# IO.net
KiCad netlist of a schematic drawn in EAGLE
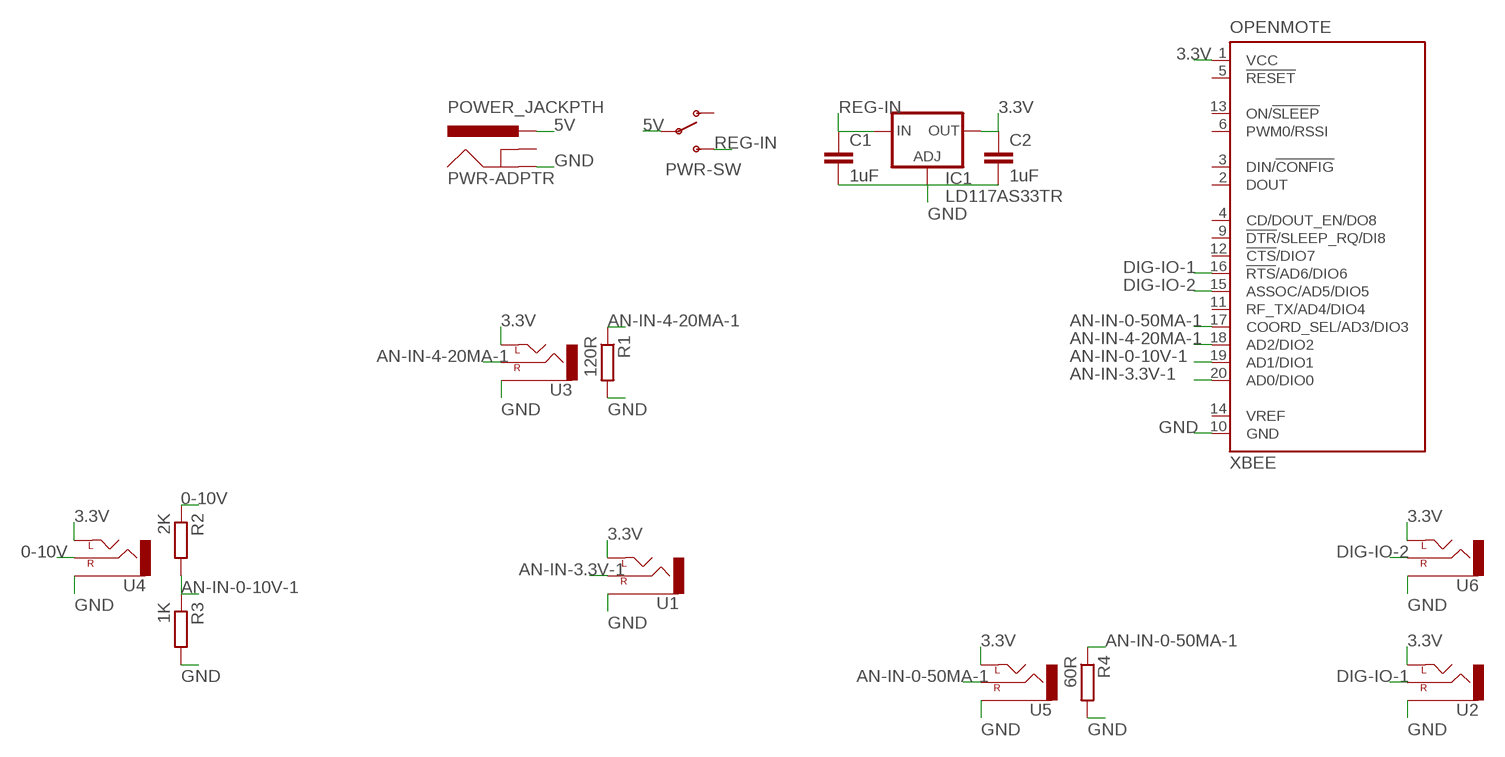
[diagram p0: schematic, sheet 1]

(export (version "E")
  (design (tool "Eeschema 10.0.6"))
  (components
    (comp (ref "C1")
      (value "1uF")
      (footprint "eagle-import:C0805")
      (libsource (lib "eagle-import") (part "C-EUC0805"))
    )
    (comp (ref "C2")
      (value "1uF")
      (footprint "eagle-import:C0805")
      (libsource (lib "eagle-import") (part "C-EUC0805"))
    )
    (comp (ref "IC1")
      (value "LD117AS33TR")
      (footprint "eagle-import:SOT223")
      (libsource (lib "eagle-import") (part "LD117A?S33TR"))
    )
    (comp (ref "OPENMOTE")
      (value "XBEE")
      (footprint "eagle-import:XBEE")
      (fields (field (name "MPN") "XBP24-Z7UIT-004"))
      (libsource (lib "eagle-import") (part "XBEE"))
    )
    (comp (ref "PWR-ADPTR")
      (value "POWER_JACKPTH")
      (footprint "eagle-import:POWER_JACK_PTH")
      (libsource (lib "eagle-import") (part "POWER_JACKPTH"))
    )
    (comp (ref "PWR-SW")
      (value "SWITCH-SPDTSMD2")
      (footprint "eagle-import:SWITCH-SPDT-SMD")
      (libsource (lib "eagle-import") (part "SWITCH-SPDTSMD2"))
    )
    (comp (ref "R1")
      (value "120R")
      (footprint "eagle-import:M0805")
      (libsource (lib "eagle-import") (part "R-EU_M0805"))
    )
    (comp (ref "R2")
      (value "2K")
      (footprint "eagle-import:M0805")
      (libsource (lib "eagle-import") (part "R-EU_M0805"))
    )
    (comp (ref "R3")
      (value "1K")
      (footprint "eagle-import:M0805")
      (libsource (lib "eagle-import") (part "R-EU_M0805"))
    )
    (comp (ref "R4")
      (value "60R")
      (footprint "eagle-import:M0805")
      (libsource (lib "eagle-import") (part "R-EU_M0805"))
    )
    (comp (ref "U1")
      (value "AUDIO-JACKSMD2")
      (footprint "eagle-import:AUDIO-JACK-3.5MM-SMD")
      (libsource (lib "eagle-import") (part "AUDIO-JACKSMD2"))
    )
    (comp (ref "U2")
      (value "AUDIO-JACKSMD2")
      (footprint "eagle-import:AUDIO-JACK-3.5MM-SMD")
      (libsource (lib "eagle-import") (part "AUDIO-JACKSMD2"))
    )
    (comp (ref "U3")
      (value "AUDIO-JACKSMD2")
      (footprint "eagle-import:AUDIO-JACK-3.5MM-SMD")
      (libsource (lib "eagle-import") (part "AUDIO-JACKSMD2"))
    )
    (comp (ref "U4")
      (value "AUDIO-JACKSMD2")
      (footprint "eagle-import:AUDIO-JACK-3.5MM-SMD")
      (libsource (lib "eagle-import") (part "AUDIO-JACKSMD2"))
    )
    (comp (ref "U5")
      (value "AUDIO-JACKSMD2")
      (footprint "eagle-import:AUDIO-JACK-3.5MM-SMD")
      (libsource (lib "eagle-import") (part "AUDIO-JACKSMD2"))
    )
    (comp (ref "U6")
      (value "AUDIO-JACKSMD2")
      (footprint "eagle-import:AUDIO-JACK-3.5MM-SMD")
      (libsource (lib "eagle-import") (part "AUDIO-JACKSMD2"))
    )
  )
  (nets
    (net (code "1") (name "/0-10V") (class "Default")
      (node (ref "R2") (pin "1") (pinfunction "1_1") (pintype "passive"))
      (node (ref "U4") (pin "RING") (pinfunction "RIGHT_RING") (pintype "bidirectional"))
    )
    (net (code "2") (name "/3.3V") (class "Default")
      (node (ref "C2") (pin "1") (pinfunction "1_1") (pintype "passive"))
      (node (ref "IC1") (pin "4") (pinfunction "OUT_4") (pintype "passive"))
      (node (ref "OPENMOTE") (pin "1") (pinfunction "VCC_1") (pintype "power_in"))
      (node (ref "U1") (pin "TIP") (pinfunction "LEFT_TIP") (pintype "bidirectional"))
      (node (ref "U2") (pin "TIP") (pinfunction "LEFT_TIP") (pintype "bidirectional"))
      (node (ref "U3") (pin "TIP") (pinfunction "LEFT_TIP") (pintype "bidirectional"))
      (node (ref "U4") (pin "TIP") (pinfunction "LEFT_TIP") (pintype "bidirectional"))
      (node (ref "U5") (pin "TIP") (pinfunction "LEFT_TIP") (pintype "bidirectional"))
      (node (ref "U6") (pin "TIP") (pinfunction "LEFT_TIP") (pintype "bidirectional"))
    )
    (net (code "3") (name "/5V") (class "Default")
      (node (ref "PWR-ADPTR") (pin "PWR") (pinfunction "PWR_PWR") (pintype "bidirectional"))
      (node (ref "PWR-SW") (pin "2") (pinfunction "P_2") (pintype "passive"))
    )
    (net (code "4") (name "/AN-IN-0-10V-1") (class "Default")
      (node (ref "OPENMOTE") (pin "19") (pinfunction "AD1/DIO1_19") (pintype "bidirectional"))
      (node (ref "R2") (pin "2") (pinfunction "2_2") (pintype "passive"))
      (node (ref "R3") (pin "1") (pinfunction "1_1") (pintype "passive"))
    )
    (net (code "5") (name "/AN-IN-0-50MA-1") (class "Default")
      (node (ref "OPENMOTE") (pin "17") (pinfunction "COORD_SEL/AD3/DIO3_17") (pintype "bidirectional"))
      (node (ref "R4") (pin "1") (pinfunction "1_1") (pintype "passive"))
      (node (ref "U5") (pin "RING") (pinfunction "RIGHT_RING") (pintype "bidirectional"))
    )
    (net (code "6") (name "/AN-IN-3.3V-1") (class "Default")
      (node (ref "OPENMOTE") (pin "20") (pinfunction "AD0/DIO0_20") (pintype "bidirectional"))
      (node (ref "U1") (pin "RING") (pinfunction "RIGHT_RING") (pintype "bidirectional"))
    )
    (net (code "7") (name "/AN-IN-4-20MA-1") (class "Default")
      (node (ref "OPENMOTE") (pin "18") (pinfunction "AD2/DIO2_18") (pintype "bidirectional"))
      (node (ref "R1") (pin "1") (pinfunction "1_1") (pintype "passive"))
      (node (ref "U3") (pin "RING") (pinfunction "RIGHT_RING") (pintype "bidirectional"))
    )
    (net (code "8") (name "/DIG-IO-1") (class "Default")
      (node (ref "OPENMOTE") (pin "16") (pinfunction "~{RTS}/AD6/DIO6_16") (pintype "bidirectional"))
      (node (ref "U2") (pin "RING") (pinfunction "RIGHT_RING") (pintype "bidirectional"))
    )
    (net (code "9") (name "/DIG-IO-2") (class "Default")
      (node (ref "OPENMOTE") (pin "15") (pinfunction "ASSOC/AD5/DIO5_15") (pintype "bidirectional"))
      (node (ref "U6") (pin "RING") (pinfunction "RIGHT_RING") (pintype "bidirectional"))
    )
    (net (code "10") (name "/GND") (class "Default")
      (node (ref "C1") (pin "2") (pinfunction "2_2") (pintype "passive"))
      (node (ref "C2") (pin "2") (pinfunction "2_2") (pintype "passive"))
      (node (ref "IC1") (pin "1") (pinfunction "ADJ_1") (pintype "input"))
      (node (ref "OPENMOTE") (pin "10") (pinfunction "GND_10") (pintype "power_in"))
      (node (ref "PWR-ADPTR") (pin "GND") (pinfunction "GND_GND") (pintype "bidirectional"))
      (node (ref "R1") (pin "2") (pinfunction "2_2") (pintype "passive"))
      (node (ref "R3") (pin "2") (pinfunction "2_2") (pintype "passive"))
      (node (ref "R4") (pin "2") (pinfunction "2_2") (pintype "passive"))
      (node (ref "U1") (pin "SLEEVE") (pinfunction "SLEEVE_SLEEVE") (pintype "bidirectional"))
      (node (ref "U2") (pin "SLEEVE") (pinfunction "SLEEVE_SLEEVE") (pintype "bidirectional"))
      (node (ref "U3") (pin "SLEEVE") (pinfunction "SLEEVE_SLEEVE") (pintype "bidirectional"))
      (node (ref "U4") (pin "SLEEVE") (pinfunction "SLEEVE_SLEEVE") (pintype "bidirectional"))
      (node (ref "U5") (pin "SLEEVE") (pinfunction "SLEEVE_SLEEVE") (pintype "bidirectional"))
      (node (ref "U6") (pin "SLEEVE") (pinfunction "SLEEVE_SLEEVE") (pintype "bidirectional"))
    )
    (net (code "11") (name "/REG-IN") (class "Default")
      (node (ref "C1") (pin "1") (pinfunction "1_1") (pintype "passive"))
      (node (ref "IC1") (pin "3") (pinfunction "IN_3") (pintype "input"))
      (node (ref "PWR-SW") (pin "3") (pinfunction "S_3") (pintype "passive"))
    )
    (net (code "12") (name "unconnected-(OPENMOTE-CD{slash}DOUT_EN{slash}DO8-Pad4)") (class "Default")
      (node (ref "OPENMOTE") (pin "4") (pinfunction "CD/DOUT_EN/DO8_4") (pintype "output"))
    )
    (net (code "13") (name "unconnected-(OPENMOTE-DIN{slash}~{CONFIG}-Pad3)") (class "Default")
      (node (ref "OPENMOTE") (pin "3") (pinfunction "DIN/~{CONFIG}_3") (pintype "input"))
    )
    (net (code "14") (name "unconnected-(OPENMOTE-DOUT-Pad2)") (class "Default")
      (node (ref "OPENMOTE") (pin "2") (pinfunction "DOUT_2") (pintype "output"))
    )
    (net (code "15") (name "unconnected-(OPENMOTE-ON{slash}~{SLEEP}-Pad13)") (class "Default")
      (node (ref "OPENMOTE") (pin "13") (pinfunction "ON/~{SLEEP}_13") (pintype "output"))
    )
    (net (code "16") (name "unconnected-(OPENMOTE-PWM0{slash}RSSI-Pad6)") (class "Default")
      (node (ref "OPENMOTE") (pin "6") (pinfunction "PWM0/RSSI_6") (pintype "output"))
    )
    (net (code "17") (name "unconnected-(OPENMOTE-RF_TX{slash}AD4{slash}DIO4-Pad11)") (class "Default")
      (node (ref "OPENMOTE") (pin "11") (pinfunction "RF_TX/AD4/DIO4_11") (pintype "bidirectional"))
    )
    (net (code "18") (name "unconnected-(OPENMOTE-VREF-Pad14)") (class "Default")
      (node (ref "OPENMOTE") (pin "14") (pinfunction "VREF_14") (pintype "input"))
    )
    (net (code "19") (name "unconnected-(OPENMOTE-~{CTS}{slash}DIO7-Pad12)") (class "Default")
      (node (ref "OPENMOTE") (pin "12") (pinfunction "~{CTS}/DIO7_12") (pintype "bidirectional"))
    )
    (net (code "20") (name "unconnected-(OPENMOTE-~{DTR}{slash}SLEEP_RQ{slash}DI8-Pad9)") (class "Default")
      (node (ref "OPENMOTE") (pin "9") (pinfunction "~{DTR}/SLEEP_RQ/DI8_9") (pintype "bidirectional"))
    )
    (net (code "21") (name "unconnected-(OPENMOTE-~{RESET}-Pad5)") (class "Default")
      (node (ref "OPENMOTE") (pin "5") (pinfunction "~{RESET}_5") (pintype "input"))
    )
    (net (code "22") (name "unconnected-(PWR-ADPTR-PadGNDBREAK)") (class "Default")
      (node (ref "PWR-ADPTR") (pin "GNDBREAK") (pinfunction "GNDBREAK_GNDBREAK") (pintype "bidirectional"))
    )
    (net (code "23") (name "unconnected-(PWR-SW-O-Pad1)") (class "Default")
      (node (ref "PWR-SW") (pin "1") (pinfunction "O_1") (pintype "passive"))
    )
  )
)
